# power-supply.net
KiCad netlist of a schematic drawn in Altium Designer
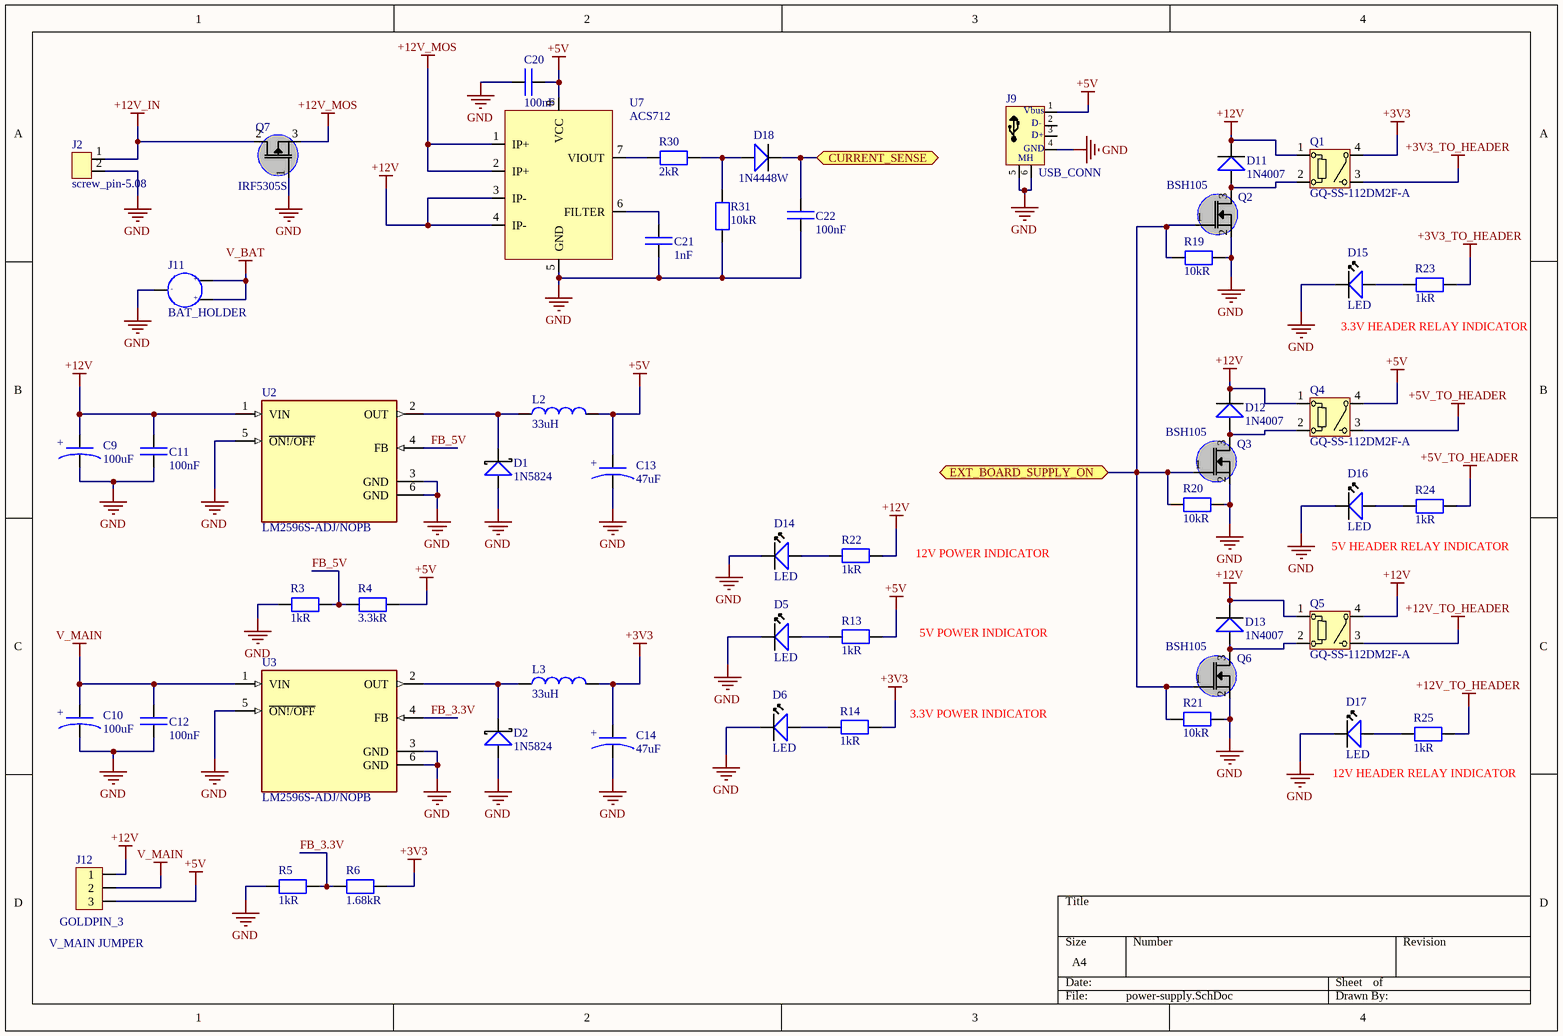
[diagram p0: power-supply.SchDoc]

(export (version "E")
  (design (tool "Eeschema 10.0.6"))
  (components
    (comp (ref "C9")
      (value "100uF")
      (footprint "C_Pol_6.3x7.7")
      (libsource (lib "przem_lib") (part "Cap_SMD_elec"))
    )
    (comp (ref "C10")
      (value "100uF")
      (footprint "C_Pol_6.3x7.7")
      (libsource (lib "przem_lib") (part "Cap_SMD_elec"))
    )
    (comp (ref "C11") (value "100nF") (footprint "C0603") (libsource (lib "przem_lib") (part "Cap_SMD")))
    (comp (ref "C12") (value "100nF") (footprint "C0603") (libsource (lib "przem_lib") (part "Cap_SMD")))
    (comp (ref "C13")
      (value "47uF")
      (footprint "C_Pol_6.3x7.7")
      (libsource (lib "przem_lib") (part "Cap_SMD_elec"))
    )
    (comp (ref "C14")
      (value "47uF")
      (footprint "C_Pol_6.3x7.7")
      (libsource (lib "przem_lib") (part "Cap_SMD_elec"))
    )
    (comp (ref "C20") (value "100nF") (footprint "C0603") (libsource (lib "przem_lib") (part "Cap_SMD")))
    (comp (ref "C21") (value "1nF") (footprint "C0603") (libsource (lib "przem_lib") (part "Cap_SMD")))
    (comp (ref "C22") (value "100nF") (footprint "C0603") (libsource (lib "przem_lib") (part "Cap_SMD")))
    (comp (ref "D1")
      (value "1N5824")
      (footprint "DO-214AA")
      (libsource (lib "przem_lib") (part "Schottky_diode"))
    )
    (comp (ref "D2")
      (value "1N5824")
      (footprint "DO-214AA")
      (libsource (lib "przem_lib") (part "Schottky_diode"))
    )
    (comp (ref "D5") (value "LED") (footprint "LED0805") (libsource (lib "przem_lib") (part "LED")))
    (comp (ref "D6") (value "LED") (footprint "LED0805") (libsource (lib "przem_lib") (part "LED")))
    (comp (ref "D11") (value "1N4007") (footprint "D_SMA") (libsource (lib "przem_lib") (part "Diode")))
    (comp (ref "D12") (value "1N4007") (footprint "D_SMA") (libsource (lib "przem_lib") (part "Diode")))
    (comp (ref "D13") (value "1N4007") (footprint "D_SMA") (libsource (lib "przem_lib") (part "Diode")))
    (comp (ref "D14") (value "LED") (footprint "LED0805") (libsource (lib "przem_lib") (part "LED")))
    (comp (ref "D15") (value "LED") (footprint "LED0805") (libsource (lib "przem_lib") (part "LED")))
    (comp (ref "D16") (value "LED") (footprint "LED0805") (libsource (lib "przem_lib") (part "LED")))
    (comp (ref "D17") (value "LED") (footprint "LED0805") (libsource (lib "przem_lib") (part "LED")))
    (comp (ref "D18") (value "1N4448W") (footprint "SOD123F") (libsource (lib "przem_lib") (part "Diode")))
    (comp (ref "J2")
      (value "screw_pin-5.08")
      (footprint "screw_pin-5.08")
      (libsource (lib "przem_lib") (part "screw_pin-5.08"))
    )
    (comp (ref "J9") (value "USB_CONN") (footprint "USB_A") (libsource (lib "przem_lib") (part "USB_CONN")))
    (comp (ref "J11")
      (value "BAT_HOLDER")
      (footprint "BAT_HOLDER")
      (libsource (lib "przem_lib") (part "BAT_HOLDER"))
    )
    (comp (ref "J12")
      (value "GOLDPIN_3")
      (footprint "PIN_HEADER_3_MALE")
      (libsource (lib "przem_lib") (part "GOLDPIN_3"))
    )
    (comp (ref "L2")
      (value "33uH")
      (footprint "SRR1260-330M")
      (libsource (lib "przem_lib") (part "Inductor"))
    )
    (comp (ref "L3")
      (value "33uH")
      (footprint "SRR1260-330M")
      (libsource (lib "przem_lib") (part "Inductor"))
    )
    (comp (ref "Q1")
      (value "GQ-SS-112DM2F-A")
      (footprint "GQ-SS-112DM2F-a")
      (libsource (lib "przem_lib") (part "GQ-SS-112DM2F-A"))
    )
    (comp (ref "Q2") (value "BSH105") (footprint "SOT23") (libsource (lib "przem_lib") (part "MOSFET_N")))
    (comp (ref "Q3") (value "BSH105") (footprint "SOT23") (libsource (lib "przem_lib") (part "MOSFET_N")))
    (comp (ref "Q4")
      (value "GQ-SS-112DM2F-A")
      (footprint "GQ-SS-112DM2F-a")
      (libsource (lib "przem_lib") (part "GQ-SS-112DM2F-A"))
    )
    (comp (ref "Q5")
      (value "GQ-SS-112DM2F-A")
      (footprint "GQ-SS-112DM2F-a")
      (libsource (lib "przem_lib") (part "GQ-SS-112DM2F-A"))
    )
    (comp (ref "Q6") (value "BSH105") (footprint "SOT23") (libsource (lib "przem_lib") (part "MOSFET_N")))
    (comp (ref "Q7") (value "IRF5305S") (footprint "DDPAK") (libsource (lib "przem_lib") (part "IRF5305S")))
    (comp (ref "R3") (value "1kR") (footprint "R0603") (libsource (lib "przem_lib") (part "Res")))
    (comp (ref "R4") (value "3.3kR") (footprint "R0603") (libsource (lib "przem_lib") (part "Res")))
    (comp (ref "R5") (value "1kR") (footprint "R0603") (libsource (lib "przem_lib") (part "Res")))
    (comp (ref "R6") (value "1.68kR") (footprint "R0603") (libsource (lib "przem_lib") (part "Res")))
    (comp (ref "R13") (value "1kR") (footprint "R0603") (libsource (lib "przem_lib") (part "Res")))
    (comp (ref "R14") (value "1kR") (footprint "R0603") (libsource (lib "przem_lib") (part "Res")))
    (comp (ref "R19") (value "10kR") (footprint "R0805") (libsource (lib "przem_lib") (part "Res")))
    (comp (ref "R20") (value "10kR") (footprint "R0805") (libsource (lib "przem_lib") (part "Res")))
    (comp (ref "R21") (value "10kR") (footprint "R0805") (libsource (lib "przem_lib") (part "Res")))
    (comp (ref "R22") (value "1kR") (footprint "R0603") (libsource (lib "przem_lib") (part "Res")))
    (comp (ref "R23") (value "1kR") (footprint "R0603") (libsource (lib "przem_lib") (part "Res")))
    (comp (ref "R24") (value "1kR") (footprint "R0603") (libsource (lib "przem_lib") (part "Res")))
    (comp (ref "R25") (value "1kR") (footprint "R0603") (libsource (lib "przem_lib") (part "Res")))
    (comp (ref "R30") (value "2kR") (footprint "R0603") (libsource (lib "przem_lib") (part "Res")))
    (comp (ref "R31") (value "10kR") (footprint "R0603") (libsource (lib "przem_lib") (part "Res")))
    (comp (ref "U2")
      (value "LM2596S-ADJ/NOPB")
      (footprint "TO-263")
      (fields (field (name "MF") "Texas Instruments"))
      (libsource (lib "przem_lib") (part "LM2596S-ADJ/NOPB"))
    )
    (comp (ref "U3")
      (value "LM2596S-ADJ/NOPB")
      (footprint "TO-263")
      (fields (field (name "MF") "Texas Instruments"))
      (libsource (lib "przem_lib") (part "LM2596S-ADJ/NOPB"))
    )
    (comp (ref "U7") (value "ACS712") (footprint "SOIC-8") (libsource (lib "przem_lib") (part "ACS712")))
  )
  (nets
    (net (code "1") (name "+3V3") (class "Default")
      (node (ref "C14") (pin "1") (pinfunction "1_1") (pintype "passive"))
      (node (ref "L3") (pin "2") (pinfunction "2_2") (pintype "passive"))
      (node (ref "Q1") (pin "4") (pinfunction "4_4") (pintype "passive"))
      (node (ref "R14") (pin "2") (pinfunction "2_2") (pintype "passive"))
      (node (ref "R6") (pin "2") (pinfunction "2_2") (pintype "passive"))
    )
    (net (code "2") (name "+3V3_TO_HEADER") (class "Default")
      (node (ref "Q1") (pin "3") (pinfunction "3_3") (pintype "passive"))
      (node (ref "R23") (pin "2") (pinfunction "2_2") (pintype "passive"))
    )
    (net (code "3") (name "+5V") (class "Default")
      (node (ref "C13") (pin "1") (pinfunction "1_1") (pintype "passive"))
      (node (ref "C20") (pin "1") (pinfunction "1_1") (pintype "passive"))
      (node (ref "J12") (pin "3") (pinfunction "3_3") (pintype "passive"))
      (node (ref "J9") (pin "1") (pinfunction "1_1") (pintype "passive"))
      (node (ref "L2") (pin "2") (pinfunction "2_2") (pintype "passive"))
      (node (ref "Q4") (pin "4") (pinfunction "4_4") (pintype "passive"))
      (node (ref "R13") (pin "2") (pinfunction "2_2") (pintype "passive"))
      (node (ref "R4") (pin "2") (pinfunction "2_2") (pintype "passive"))
      (node (ref "U7") (pin "8") (pinfunction "VCC_8") (pintype "passive"))
    )
    (net (code "4") (name "+5V_TO_HEADER") (class "Default")
      (node (ref "Q4") (pin "3") (pinfunction "3_3") (pintype "passive"))
      (node (ref "R24") (pin "2") (pinfunction "2_2") (pintype "passive"))
    )
    (net (code "5") (name "+12V") (class "Default")
      (node (ref "C11") (pin "2") (pinfunction "2_2") (pintype "passive"))
      (node (ref "C9") (pin "1") (pinfunction "1_1") (pintype "passive"))
      (node (ref "D11") (pin "K") (pinfunction "K_K") (pintype "passive"))
      (node (ref "D12") (pin "K") (pinfunction "K_K") (pintype "passive"))
      (node (ref "D13") (pin "K") (pinfunction "K_K") (pintype "passive"))
      (node (ref "J12") (pin "1") (pinfunction "1_1") (pintype "passive"))
      (node (ref "Q1") (pin "1") (pinfunction "1_1") (pintype "passive"))
      (node (ref "Q4") (pin "1") (pinfunction "1_1") (pintype "passive"))
      (node (ref "Q5") (pin "1") (pinfunction "1_1") (pintype "passive"))
      (node (ref "Q5") (pin "4") (pinfunction "4_4") (pintype "passive"))
      (node (ref "R22") (pin "2") (pinfunction "2_2") (pintype "passive"))
      (node (ref "U2") (pin "1") (pinfunction "VIN_1") (pintype "input"))
      (node (ref "U7") (pin "3") (pinfunction "IP-_3") (pintype "passive"))
      (node (ref "U7") (pin "4") (pinfunction "IP-_4") (pintype "passive"))
    )
    (net (code "6") (name "+12V_IN") (class "Default")
      (node (ref "J2") (pin "1") (pinfunction "1_1") (pintype "passive"))
      (node (ref "Q7") (pin "2") (pinfunction "2_2") (pintype "passive"))
    )
    (net (code "7") (name "+12V_MOS") (class "Default")
      (node (ref "Q7") (pin "3") (pinfunction "3_3") (pintype "passive"))
      (node (ref "U7") (pin "1") (pinfunction "IP+_1") (pintype "passive"))
      (node (ref "U7") (pin "2") (pinfunction "IP+_2") (pintype "passive"))
    )
    (net (code "8") (name "+12V_TO_HEADER") (class "Default")
      (node (ref "Q5") (pin "3") (pinfunction "3_3") (pintype "passive"))
      (node (ref "R25") (pin "2") (pinfunction "2_2") (pintype "passive"))
    )
    (net (code "9") (name "/CURRENT_SENSE") (class "Default")
      (node (ref "C22") (pin "2") (pinfunction "2_2") (pintype "passive"))
      (node (ref "D18") (pin "K") (pinfunction "K_K") (pintype "passive"))
    )
    (net (code "10") (name "/EXT_BOARD_SUPPLY_ON") (class "Default")
      (node (ref "Q2") (pin "1") (pinfunction "G_1") (pintype "passive"))
      (node (ref "Q3") (pin "1") (pinfunction "G_1") (pintype "passive"))
      (node (ref "Q6") (pin "1") (pinfunction "G_1") (pintype "passive"))
      (node (ref "R19") (pin "1") (pinfunction "1_1") (pintype "passive"))
      (node (ref "R20") (pin "1") (pinfunction "1_1") (pintype "passive"))
      (node (ref "R21") (pin "1") (pinfunction "1_1") (pintype "passive"))
    )
    (net (code "11") (name "/FB_3.3V") (class "Default")
      (node (ref "R5") (pin "2") (pinfunction "2_2") (pintype "passive"))
      (node (ref "R6") (pin "1") (pinfunction "1_1") (pintype "passive"))
      (node (ref "U3") (pin "4") (pinfunction "FB_4") (pintype "input"))
    )
    (net (code "12") (name "/FB_5V") (class "Default")
      (node (ref "R3") (pin "2") (pinfunction "2_2") (pintype "passive"))
      (node (ref "R4") (pin "1") (pinfunction "1_1") (pintype "passive"))
      (node (ref "U2") (pin "4") (pinfunction "FB_4") (pintype "input"))
    )
    (net (code "13") (name "GND") (class "Default")
      (node (ref "C10") (pin "2") (pinfunction "2_2") (pintype "passive"))
      (node (ref "C11") (pin "1") (pinfunction "1_1") (pintype "passive"))
      (node (ref "C12") (pin "1") (pinfunction "1_1") (pintype "passive"))
      (node (ref "C13") (pin "2") (pinfunction "2_2") (pintype "passive"))
      (node (ref "C14") (pin "2") (pinfunction "2_2") (pintype "passive"))
      (node (ref "C20") (pin "2") (pinfunction "2_2") (pintype "passive"))
      (node (ref "C21") (pin "1") (pinfunction "1_1") (pintype "passive"))
      (node (ref "C22") (pin "1") (pinfunction "1_1") (pintype "passive"))
      (node (ref "C9") (pin "2") (pinfunction "2_2") (pintype "passive"))
      (node (ref "D1") (pin "A") (pinfunction "A_A") (pintype "passive"))
      (node (ref "D14") (pin "K") (pinfunction "K_K") (pintype "passive"))
      (node (ref "D15") (pin "K") (pinfunction "K_K") (pintype "passive"))
      (node (ref "D16") (pin "K") (pinfunction "K_K") (pintype "passive"))
      (node (ref "D17") (pin "K") (pinfunction "K_K") (pintype "passive"))
      (node (ref "D2") (pin "A") (pinfunction "A_A") (pintype "passive"))
      (node (ref "D5") (pin "K") (pinfunction "K_K") (pintype "passive"))
      (node (ref "D6") (pin "K") (pinfunction "K_K") (pintype "passive"))
      (node (ref "J11") (pin "3") (pinfunction "-_3") (pintype "passive"))
      (node (ref "J2") (pin "2") (pinfunction "2_2") (pintype "passive"))
      (node (ref "J9") (pin "4") (pinfunction "4_4") (pintype "passive"))
      (node (ref "J9") (pin "5") (pinfunction "5_5") (pintype "passive"))
      (node (ref "J9") (pin "6") (pinfunction "6_6") (pintype "passive"))
      (node (ref "Q2") (pin "2") (pinfunction "2_2") (pintype "passive"))
      (node (ref "Q3") (pin "2") (pinfunction "2_2") (pintype "passive"))
      (node (ref "Q6") (pin "2") (pinfunction "2_2") (pintype "passive"))
      (node (ref "Q7") (pin "1") (pinfunction "G_1") (pintype "passive"))
      (node (ref "R19") (pin "2") (pinfunction "2_2") (pintype "passive"))
      (node (ref "R20") (pin "2") (pinfunction "2_2") (pintype "passive"))
      (node (ref "R21") (pin "2") (pinfunction "2_2") (pintype "passive"))
      (node (ref "R3") (pin "1") (pinfunction "1_1") (pintype "passive"))
      (node (ref "R31") (pin "1") (pinfunction "1_1") (pintype "passive"))
      (node (ref "R5") (pin "1") (pinfunction "1_1") (pintype "passive"))
      (node (ref "U2") (pin "3") (pinfunction "GND_3") (pintype "power_in"))
      (node (ref "U2") (pin "5") (pinfunction "~{ON!/OFF}_5") (pintype "input"))
      (node (ref "U2") (pin "6") (pinfunction "GND_6") (pintype "power_in"))
      (node (ref "U3") (pin "3") (pinfunction "GND_3") (pintype "power_in"))
      (node (ref "U3") (pin "5") (pinfunction "~{ON!/OFF}_5") (pintype "input"))
      (node (ref "U3") (pin "6") (pinfunction "GND_6") (pintype "power_in"))
      (node (ref "U7") (pin "5") (pinfunction "GND_5") (pintype "passive"))
    )
    (net (code "14") (name "Net-(D5-PadA)") (class "Default")
      (node (ref "D5") (pin "A") (pinfunction "A_A") (pintype "passive"))
      (node (ref "R13") (pin "1") (pinfunction "1_1") (pintype "passive"))
    )
    (net (code "15") (name "Net-(D6-PadA)") (class "Default")
      (node (ref "D6") (pin "A") (pinfunction "A_A") (pintype "passive"))
      (node (ref "R14") (pin "1") (pinfunction "1_1") (pintype "passive"))
    )
    (net (code "16") (name "Net-(D11-PadA)") (class "Default")
      (node (ref "D11") (pin "A") (pinfunction "A_A") (pintype "passive"))
      (node (ref "Q1") (pin "2") (pinfunction "2_2") (pintype "passive"))
      (node (ref "Q2") (pin "3") (pinfunction "3_3") (pintype "passive"))
    )
    (net (code "17") (name "Net-(D12-PadA)") (class "Default")
      (node (ref "D12") (pin "A") (pinfunction "A_A") (pintype "passive"))
      (node (ref "Q3") (pin "3") (pinfunction "3_3") (pintype "passive"))
      (node (ref "Q4") (pin "2") (pinfunction "2_2") (pintype "passive"))
    )
    (net (code "18") (name "Net-(D13-PadA)") (class "Default")
      (node (ref "D13") (pin "A") (pinfunction "A_A") (pintype "passive"))
      (node (ref "Q5") (pin "2") (pinfunction "2_2") (pintype "passive"))
      (node (ref "Q6") (pin "3") (pinfunction "3_3") (pintype "passive"))
    )
    (net (code "19") (name "Net-(D14-PadA)") (class "Default")
      (node (ref "D14") (pin "A") (pinfunction "A_A") (pintype "passive"))
      (node (ref "R22") (pin "1") (pinfunction "1_1") (pintype "passive"))
    )
    (net (code "20") (name "Net-(D15-PadA)") (class "Default")
      (node (ref "D15") (pin "A") (pinfunction "A_A") (pintype "passive"))
      (node (ref "R23") (pin "1") (pinfunction "1_1") (pintype "passive"))
    )
    (net (code "21") (name "Net-(D16-PadA)") (class "Default")
      (node (ref "D16") (pin "A") (pinfunction "A_A") (pintype "passive"))
      (node (ref "R24") (pin "1") (pinfunction "1_1") (pintype "passive"))
    )
    (net (code "22") (name "Net-(D17-PadA)") (class "Default")
      (node (ref "D17") (pin "A") (pinfunction "A_A") (pintype "passive"))
      (node (ref "R25") (pin "1") (pinfunction "1_1") (pintype "passive"))
    )
    (net (code "23") (name "Net-(D18-PadA)") (class "Default")
      (node (ref "D18") (pin "A") (pinfunction "A_A") (pintype "passive"))
      (node (ref "R30") (pin "1") (pinfunction "1_1") (pintype "passive"))
      (node (ref "R31") (pin "2") (pinfunction "2_2") (pintype "passive"))
    )
    (net (code "24") (name "Net-(U2-OUT)") (class "Default")
      (node (ref "D1") (pin "K") (pinfunction "K_K") (pintype "passive"))
      (node (ref "L2") (pin "1") (pinfunction "1_1") (pintype "passive"))
      (node (ref "U2") (pin "2") (pinfunction "OUT_2") (pintype "output"))
    )
    (net (code "25") (name "Net-(U3-OUT)") (class "Default")
      (node (ref "D2") (pin "K") (pinfunction "K_K") (pintype "passive"))
      (node (ref "L3") (pin "1") (pinfunction "1_1") (pintype "passive"))
      (node (ref "U3") (pin "2") (pinfunction "OUT_2") (pintype "output"))
    )
    (net (code "26") (name "Net-(U7-FILTER)") (class "Default")
      (node (ref "C21") (pin "2") (pinfunction "2_2") (pintype "passive"))
      (node (ref "U7") (pin "6") (pinfunction "FILTER_6") (pintype "passive"))
    )
    (net (code "27") (name "Net-(U7-VIOUT)") (class "Default")
      (node (ref "R30") (pin "2") (pinfunction "2_2") (pintype "passive"))
      (node (ref "U7") (pin "7") (pinfunction "VIOUT_7") (pintype "passive"))
    )
    (net (code "28") (name "V_BAT") (class "Default")
      (node (ref "J11") (pin "1") (pinfunction "+_1") (pintype "passive"))
      (node (ref "J11") (pin "2") (pinfunction "+_2") (pintype "passive"))
    )
    (net (code "29") (name "V_MAIN") (class "Default")
      (node (ref "C10") (pin "1") (pinfunction "1_1") (pintype "passive"))
      (node (ref "C12") (pin "2") (pinfunction "2_2") (pintype "passive"))
      (node (ref "J12") (pin "2") (pinfunction "2_2") (pintype "passive"))
      (node (ref "U3") (pin "1") (pinfunction "VIN_1") (pintype "input"))
    )
    (net (code "30") (name "unconnected-(J9-D+-Pad3)") (class "Default")
      (node (ref "J9") (pin "3") (pinfunction "D+_3") (pintype "passive"))
    )
    (net (code "31") (name "unconnected-(J9-D--Pad2)") (class "Default")
      (node (ref "J9") (pin "2") (pinfunction "D-_2") (pintype "passive"))
    )
  )
)
